# input2.net
KiCad netlist of a schematic drawn in Altium Designer
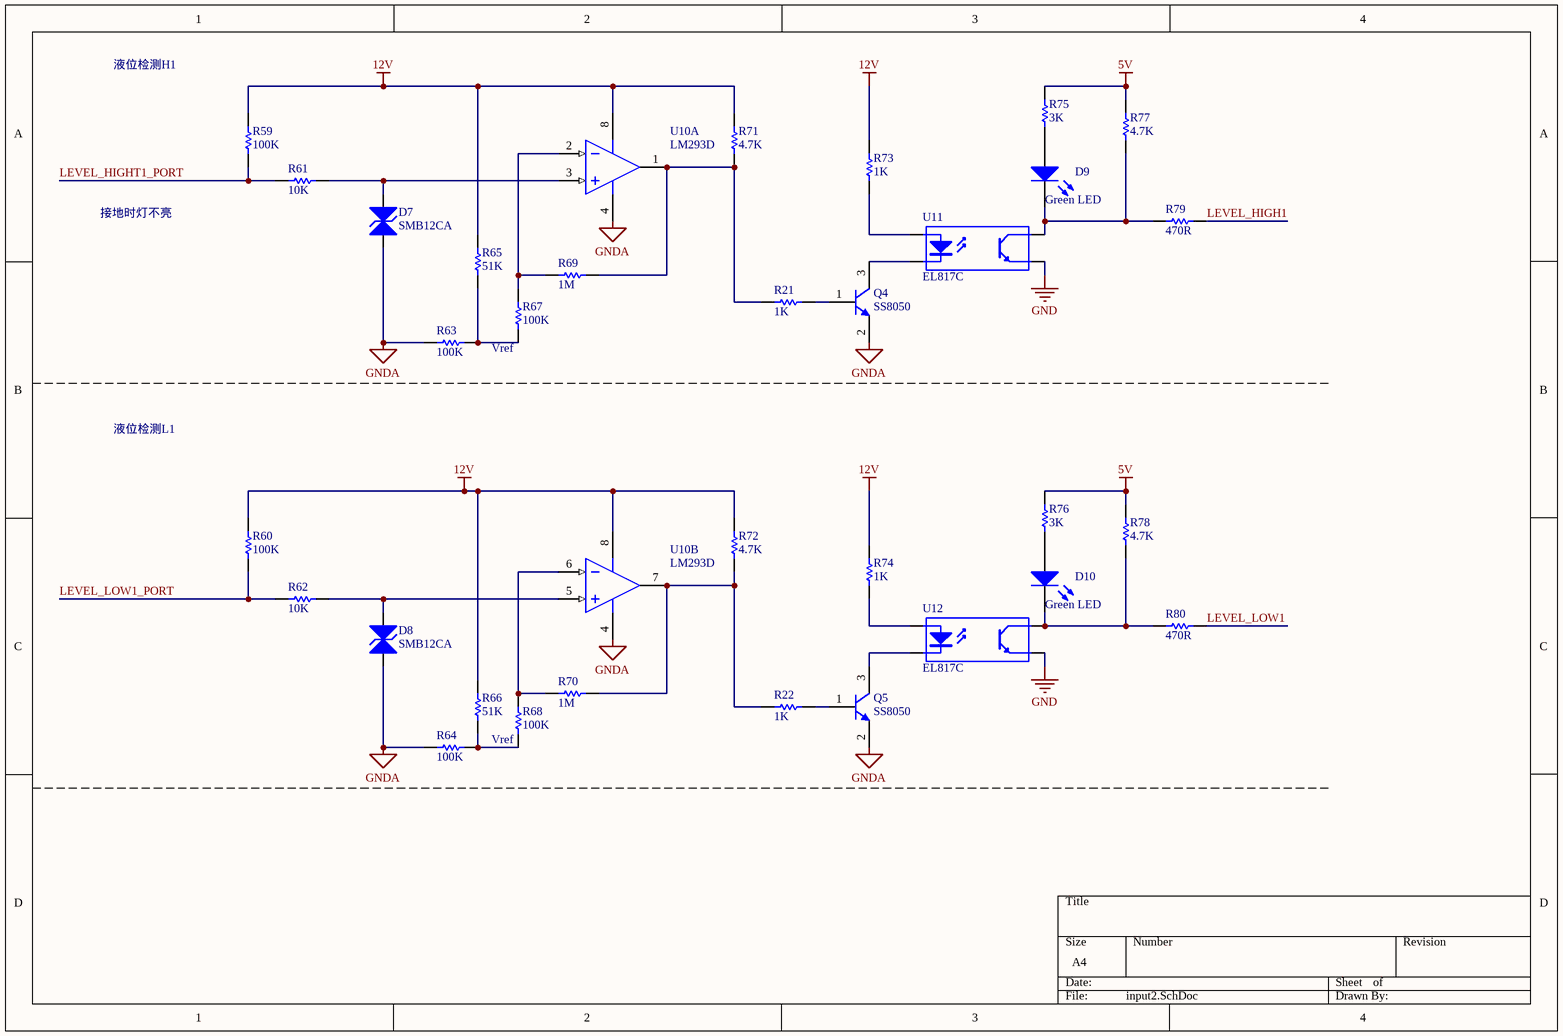
[diagram p0: input2.SchDoc]

(export (version "E")
  (design (tool "Eeschema 10.0.6"))
  (components
    (comp (ref "D7")
      (value "SMB12CA")
      (footprint "SMB")
      (description "Bi-dir TVS Diode")
      (fields (field (name "PUBLISHER") "Altium Limited"))
      (libsource (lib "UserLib") (part "Bi-dir TVS Diode"))
    )
    (comp (ref "D8")
      (value "SMB12CA")
      (footprint "SMB")
      (description "Bi-dir TVS Diode")
      (fields (field (name "PUBLISHER") "Altium Limited"))
      (libsource (lib "UserLib") (part "Bi-dir TVS Diode"))
    )
    (comp (ref "D9")
      (value "Green LED")
      (footprint "LED254A")
      (description "Green LED ,SIP, Dia =3mm")
      (fields (field (name "PUBLISHER") "Altium Limited"))
      (libsource (lib "Miscellaneous Devices") (part "LED1"))
    )
    (comp (ref "D10")
      (value "Green LED")
      (footprint "LED254A")
      (description "Green LED ,SIP, Dia =3mm")
      (fields (field (name "PUBLISHER") "Altium Limited"))
      (libsource (lib "Miscellaneous Devices") (part "LED1"))
    )
    (comp (ref "Q4")
      (value "SS8050")
      (footprint "SOT-23_N")
      (description "NPN BISS Transistor")
      (fields (field (name "PUBLISHER") "Altium Limited"))
      (libsource (lib "Philips Discrete BJT - Low Power") (part "PMMT491A"))
    )
    (comp (ref "Q5")
      (value "SS8050")
      (footprint "SOT-23_N")
      (description "NPN BISS Transistor")
      (fields (field (name "PUBLISHER") "Altium Limited"))
      (libsource (lib "Philips Discrete BJT - Low Power") (part "PMMT491A"))
    )
    (comp (ref "R21")
      (value "1K")
      (footprint "RESC2012M")
      (description "Resistor")
      (fields (field (name "PUBLISHER") "Altium Limited"))
      (libsource (lib "Miscellaneous Devices") (part "Res1"))
    )
    (comp (ref "R22")
      (value "1K")
      (footprint "RESC2012M")
      (description "Resistor")
      (fields (field (name "PUBLISHER") "Altium Limited"))
      (libsource (lib "Miscellaneous Devices") (part "Res1"))
    )
    (comp (ref "R59")
      (value "100K")
      (footprint "RESC2012M")
      (description "Resistor")
      (fields (field (name "PUBLISHER") "Altium Limited"))
      (libsource (lib "Miscellaneous Devices") (part "Res1"))
    )
    (comp (ref "R60")
      (value "100K")
      (footprint "RESC2012M")
      (description "Resistor")
      (fields (field (name "PUBLISHER") "Altium Limited"))
      (libsource (lib "Miscellaneous Devices") (part "Res1"))
    )
    (comp (ref "R61")
      (value "10K")
      (footprint "RESC2012M")
      (description "Resistor")
      (fields (field (name "PUBLISHER") "Altium Limited"))
      (libsource (lib "Miscellaneous Devices") (part "Res1"))
    )
    (comp (ref "R62")
      (value "10K")
      (footprint "RESC2012M")
      (description "Resistor")
      (fields (field (name "PUBLISHER") "Altium Limited"))
      (libsource (lib "Miscellaneous Devices") (part "Res1"))
    )
    (comp (ref "R63")
      (value "100K")
      (footprint "RESC2012M")
      (description "Resistor")
      (fields (field (name "PUBLISHER") "Altium Limited"))
      (libsource (lib "Miscellaneous Devices") (part "Res1"))
    )
    (comp (ref "R64")
      (value "100K")
      (footprint "RESC2012M")
      (description "Resistor")
      (fields (field (name "PUBLISHER") "Altium Limited"))
      (libsource (lib "Miscellaneous Devices") (part "Res1"))
    )
    (comp (ref "R65")
      (value "51K")
      (footprint "RESC2012M")
      (description "Resistor")
      (fields (field (name "PUBLISHER") "Altium Limited"))
      (libsource (lib "Miscellaneous Devices") (part "Res1"))
    )
    (comp (ref "R66")
      (value "51K")
      (footprint "RESC2012M")
      (description "Resistor")
      (fields (field (name "PUBLISHER") "Altium Limited"))
      (libsource (lib "Miscellaneous Devices") (part "Res1"))
    )
    (comp (ref "R67")
      (value "100K")
      (footprint "RESC2012M")
      (description "Resistor")
      (fields (field (name "PUBLISHER") "Altium Limited"))
      (libsource (lib "Miscellaneous Devices") (part "Res1"))
    )
    (comp (ref "R68")
      (value "100K")
      (footprint "RESC2012M")
      (description "Resistor")
      (fields (field (name "PUBLISHER") "Altium Limited"))
      (libsource (lib "Miscellaneous Devices") (part "Res1"))
    )
    (comp (ref "R69")
      (value "1M")
      (footprint "RESC2012M")
      (description "Resistor")
      (fields (field (name "PUBLISHER") "Altium Limited"))
      (libsource (lib "Miscellaneous Devices") (part "Res1"))
    )
    (comp (ref "R70")
      (value "1M")
      (footprint "RESC2012M")
      (description "Resistor")
      (fields (field (name "PUBLISHER") "Altium Limited"))
      (libsource (lib "Miscellaneous Devices") (part "Res1"))
    )
    (comp (ref "R71")
      (value "4.7K")
      (footprint "RESC2012M")
      (description "Resistor")
      (fields (field (name "PUBLISHER") "Altium Limited"))
      (libsource (lib "Miscellaneous Devices") (part "Res1"))
    )
    (comp (ref "R72")
      (value "4.7K")
      (footprint "RESC2012M")
      (description "Resistor")
      (fields (field (name "PUBLISHER") "Altium Limited"))
      (libsource (lib "Miscellaneous Devices") (part "Res1"))
    )
    (comp (ref "R73")
      (value "1K")
      (footprint "RESC2012M")
      (description "Resistor")
      (fields (field (name "PUBLISHER") "Altium Limited"))
      (libsource (lib "Miscellaneous Devices") (part "Res1"))
    )
    (comp (ref "R74")
      (value "1K")
      (footprint "RESC2012M")
      (description "Resistor")
      (fields (field (name "PUBLISHER") "Altium Limited"))
      (libsource (lib "Miscellaneous Devices") (part "Res1"))
    )
    (comp (ref "R75")
      (value "3K")
      (footprint "RESC2012M")
      (description "Resistor")
      (fields (field (name "PUBLISHER") "Altium Limited"))
      (libsource (lib "Miscellaneous Devices") (part "Res1"))
    )
    (comp (ref "R76")
      (value "3K")
      (footprint "RESC2012M")
      (description "Resistor")
      (fields (field (name "PUBLISHER") "Altium Limited"))
      (libsource (lib "Miscellaneous Devices") (part "Res1"))
    )
    (comp (ref "R77")
      (value "4.7K")
      (footprint "RESC2012M")
      (description "Resistor")
      (fields (field (name "PUBLISHER") "Altium Limited"))
      (libsource (lib "Miscellaneous Devices") (part "Res1"))
    )
    (comp (ref "R78")
      (value "4.7K")
      (footprint "RESC2012M")
      (description "Resistor")
      (fields (field (name "PUBLISHER") "Altium Limited"))
      (libsource (lib "Miscellaneous Devices") (part "Res1"))
    )
    (comp (ref "R79")
      (value "470R")
      (footprint "RESC2012M")
      (description "Resistor")
      (fields (field (name "PUBLISHER") "Altium Limited"))
      (libsource (lib "Miscellaneous Devices") (part "Res1"))
    )
    (comp (ref "R80")
      (value "470R")
      (footprint "RESC2012M")
      (description "Resistor")
      (fields (field (name "PUBLISHER") "Altium Limited"))
      (libsource (lib "Miscellaneous Devices") (part "Res1"))
    )
    (comp (ref "U10")
      (value "LM293D")
      (footprint "SO8_N")
      (description "Low-Power Dual Voltage Comparator")
      (fields (field (name "PUBLISHER") "Altium Limited"))
      (libsource (lib "ST Analog Comparator") (part "LM393AD"))
    )
    (comp (ref "U11")
      (value "EL817C")
      (footprint "SO-4LA")
      (description "4-Pin Phototransistor Optocoupler")
      (fields (field (name "PUBLISHER") "Altium Limited"))
      (libsource (lib "Miscellaneous Devices") (part "Optoisolator1"))
    )
    (comp (ref "U12")
      (value "EL817C")
      (footprint "SO-4LA")
      (description "4-Pin Phototransistor Optocoupler")
      (fields (field (name "PUBLISHER") "Altium Limited"))
      (libsource (lib "Miscellaneous Devices") (part "Optoisolator1"))
    )
  )
  (nets
    (net (code "1") (name "/LEVEL_HIGH1") (class "Default")
      (node (ref "R79") (pin "2") (pinfunction "2_2") (pintype "passive"))
    )
    (net (code "2") (name "/LEVEL_HIGHT1_PORT") (class "Default")
      (node (ref "R59") (pin "1") (pinfunction "1_1") (pintype "passive"))
      (node (ref "R61") (pin "2") (pinfunction "2_2") (pintype "passive"))
    )
    (net (code "3") (name "/LEVEL_LOW1") (class "Default")
      (node (ref "R80") (pin "2") (pinfunction "2_2") (pintype "passive"))
    )
    (net (code "4") (name "/LEVEL_LOW1_PORT") (class "Default")
      (node (ref "R60") (pin "1") (pinfunction "1_1") (pintype "passive"))
      (node (ref "R62") (pin "2") (pinfunction "2_2") (pintype "passive"))
    )
    (net (code "5") (name "5V") (class "Default")
      (node (ref "R75") (pin "1") (pinfunction "1_1") (pintype "passive"))
      (node (ref "R76") (pin "1") (pinfunction "1_1") (pintype "passive"))
      (node (ref "R77") (pin "2") (pinfunction "2_2") (pintype "passive"))
      (node (ref "R78") (pin "2") (pinfunction "2_2") (pintype "passive"))
    )
    (net (code "6") (name "12V") (class "Default")
      (node (ref "R59") (pin "2") (pinfunction "2_2") (pintype "passive"))
      (node (ref "R60") (pin "2") (pinfunction "2_2") (pintype "passive"))
      (node (ref "R65") (pin "2") (pinfunction "2_2") (pintype "passive"))
      (node (ref "R66") (pin "2") (pinfunction "2_2") (pintype "passive"))
      (node (ref "R71") (pin "1") (pinfunction "1_1") (pintype "passive"))
      (node (ref "R72") (pin "2") (pinfunction "2_2") (pintype "passive"))
      (node (ref "R73") (pin "2") (pinfunction "2_2") (pintype "passive"))
      (node (ref "R74") (pin "1") (pinfunction "1_1") (pintype "passive"))
      (node (ref "U10") (pin "8") (pinfunction "V+_8") (pintype "power_in"))
    )
    (net (code "7") (name "GND") (class "Default")
      (node (ref "U11") (pin "3") (pinfunction "E_3") (pintype "passive"))
      (node (ref "U12") (pin "3") (pinfunction "E_3") (pintype "passive"))
    )
    (net (code "8") (name "GNDA") (class "Default")
      (node (ref "D7") (pin "1") (pinfunction "A_1") (pintype "passive"))
      (node (ref "D8") (pin "1") (pinfunction "A_1") (pintype "passive"))
      (node (ref "Q4") (pin "2") (pinfunction "E_2") (pintype "passive"))
      (node (ref "Q5") (pin "2") (pinfunction "E_2") (pintype "passive"))
      (node (ref "R63") (pin "1") (pinfunction "1_1") (pintype "passive"))
      (node (ref "R64") (pin "1") (pinfunction "1_1") (pintype "passive"))
      (node (ref "U10") (pin "4") (pinfunction "V-_4") (pintype "power_in"))
    )
    (net (code "9") (name "Net-(D7-K)") (class "Default")
      (node (ref "D7") (pin "2") (pinfunction "K_2") (pintype "passive"))
      (node (ref "R61") (pin "1") (pinfunction "1_1") (pintype "passive"))
      (node (ref "U10") (pin "3") (pinfunction "IN+_3") (pintype "input"))
    )
    (net (code "10") (name "Net-(D8-K)") (class "Default")
      (node (ref "D8") (pin "2") (pinfunction "K_2") (pintype "passive"))
      (node (ref "R62") (pin "1") (pinfunction "1_1") (pintype "passive"))
      (node (ref "U10") (pin "5") (pinfunction "IN+_5") (pintype "input"))
    )
    (net (code "11") (name "Net-(D9-A)") (class "Default")
      (node (ref "D9") (pin "1") (pinfunction "A_1") (pintype "passive"))
      (node (ref "R75") (pin "2") (pinfunction "2_2") (pintype "passive"))
    )
    (net (code "12") (name "Net-(D9-K)") (class "Default")
      (node (ref "D9") (pin "2") (pinfunction "K_2") (pintype "passive"))
      (node (ref "R77") (pin "1") (pinfunction "1_1") (pintype "passive"))
      (node (ref "R79") (pin "1") (pinfunction "1_1") (pintype "passive"))
      (node (ref "U11") (pin "4") (pinfunction "C_4") (pintype "passive"))
    )
    (net (code "13") (name "Net-(D10-A)") (class "Default")
      (node (ref "D10") (pin "1") (pinfunction "A_1") (pintype "passive"))
      (node (ref "R76") (pin "2") (pinfunction "2_2") (pintype "passive"))
    )
    (net (code "14") (name "Net-(D10-K)") (class "Default")
      (node (ref "D10") (pin "2") (pinfunction "K_2") (pintype "passive"))
      (node (ref "R78") (pin "1") (pinfunction "1_1") (pintype "passive"))
      (node (ref "R80") (pin "1") (pinfunction "1_1") (pintype "passive"))
      (node (ref "U12") (pin "4") (pinfunction "C_4") (pintype "passive"))
    )
    (net (code "15") (name "Net-(Q4-B)") (class "Default")
      (node (ref "Q4") (pin "1") (pinfunction "B_1") (pintype "passive"))
      (node (ref "R21") (pin "2") (pinfunction "2_2") (pintype "passive"))
    )
    (net (code "16") (name "Net-(Q4-C)") (class "Default")
      (node (ref "Q4") (pin "3") (pinfunction "C_3") (pintype "passive"))
      (node (ref "U11") (pin "2") (pinfunction "K_2") (pintype "passive"))
    )
    (net (code "17") (name "Net-(Q5-B)") (class "Default")
      (node (ref "Q5") (pin "1") (pinfunction "B_1") (pintype "passive"))
      (node (ref "R22") (pin "2") (pinfunction "2_2") (pintype "passive"))
    )
    (net (code "18") (name "Net-(Q5-C)") (class "Default")
      (node (ref "Q5") (pin "3") (pinfunction "C_3") (pintype "passive"))
      (node (ref "U12") (pin "2") (pinfunction "K_2") (pintype "passive"))
    )
    (net (code "19") (name "Net-(R63-Pad2)") (class "Default")
      (node (ref "R63") (pin "2") (pinfunction "2_2") (pintype "passive"))
      (node (ref "R65") (pin "1") (pinfunction "1_1") (pintype "passive"))
      (node (ref "R67") (pin "2") (pinfunction "2_2") (pintype "passive"))
    )
    (net (code "20") (name "Net-(R64-Pad2)") (class "Default")
      (node (ref "R64") (pin "2") (pinfunction "2_2") (pintype "passive"))
      (node (ref "R66") (pin "1") (pinfunction "1_1") (pintype "passive"))
      (node (ref "R68") (pin "1") (pinfunction "1_1") (pintype "passive"))
    )
    (net (code "21") (name "Net-(U10A-IN-)") (class "Default")
      (node (ref "R67") (pin "1") (pinfunction "1_1") (pintype "passive"))
      (node (ref "R69") (pin "1") (pinfunction "1_1") (pintype "passive"))
      (node (ref "U10") (pin "2") (pinfunction "IN-_2") (pintype "input"))
    )
    (net (code "22") (name "Net-(U10A-OUT)") (class "Default")
      (node (ref "R21") (pin "1") (pinfunction "1_1") (pintype "passive"))
      (node (ref "R69") (pin "2") (pinfunction "2_2") (pintype "passive"))
      (node (ref "R71") (pin "2") (pinfunction "2_2") (pintype "passive"))
      (node (ref "U10") (pin "1") (pinfunction "OUT_1") (pintype "open_collector"))
    )
    (net (code "23") (name "Net-(U10B-IN-)") (class "Default")
      (node (ref "R68") (pin "2") (pinfunction "2_2") (pintype "passive"))
      (node (ref "R70") (pin "1") (pinfunction "1_1") (pintype "passive"))
      (node (ref "U10") (pin "6") (pinfunction "IN-_6") (pintype "input"))
    )
    (net (code "24") (name "Net-(U10B-OUT)") (class "Default")
      (node (ref "R22") (pin "1") (pinfunction "1_1") (pintype "passive"))
      (node (ref "R70") (pin "2") (pinfunction "2_2") (pintype "passive"))
      (node (ref "R72") (pin "1") (pinfunction "1_1") (pintype "passive"))
      (node (ref "U10") (pin "7") (pinfunction "OUT_7") (pintype "open_collector"))
    )
    (net (code "25") (name "Net-(U11-A)") (class "Default")
      (node (ref "R73") (pin "1") (pinfunction "1_1") (pintype "passive"))
      (node (ref "U11") (pin "1") (pinfunction "A_1") (pintype "passive"))
    )
    (net (code "26") (name "Net-(U12-A)") (class "Default")
      (node (ref "R74") (pin "2") (pinfunction "2_2") (pintype "passive"))
      (node (ref "U12") (pin "1") (pinfunction "A_1") (pintype "passive"))
    )
  )
)
